# Supply.net
KiCad netlist of a schematic drawn in Altium Designer
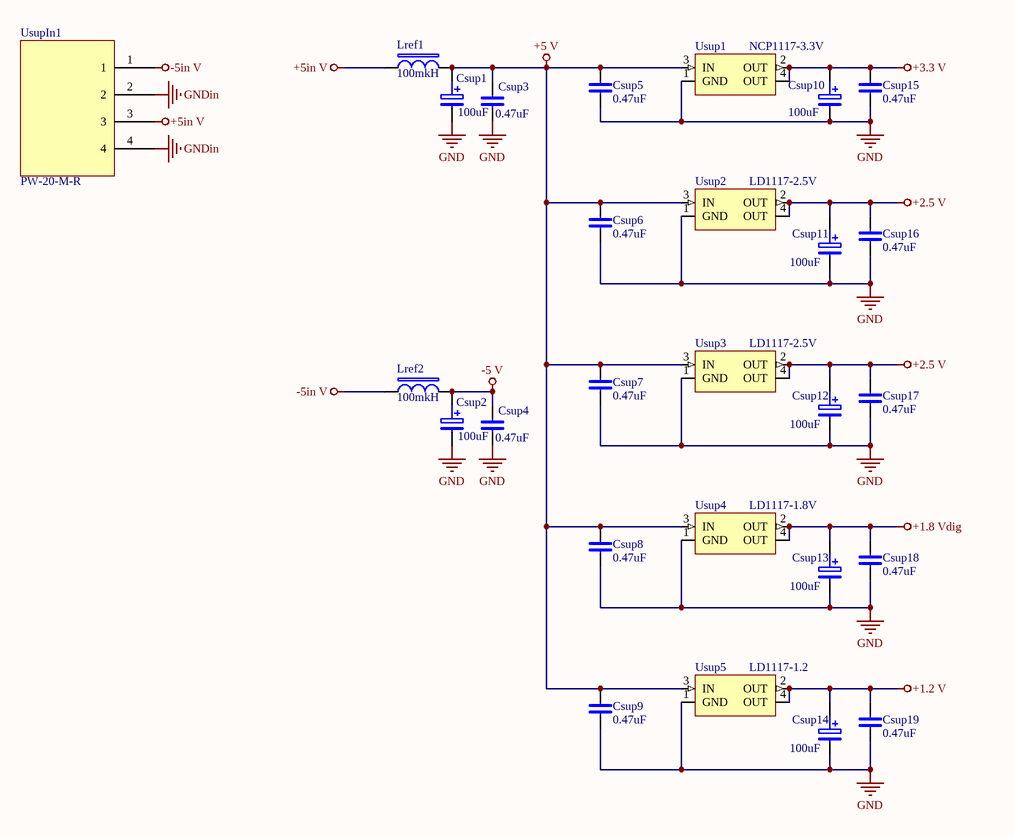
[diagram p0: Supply.SchDoc]

(export (version "E")
  (design (tool "Eeschema 10.0.6"))
  (components
    (comp (ref "Csup1") (value "100uF") (footprint "CEL-SMD300") (libsource (lib "*") (part "C POL")))
    (comp (ref "Csup2") (value "100uF") (footprint "CEL-SMD300") (libsource (lib "*") (part "C POL")))
    (comp (ref "Csup3") (value "0.47uF") (footprint "chip0603") (libsource (lib "*") (part "C")))
    (comp (ref "Csup4") (value "0.47uF") (footprint "chip0603") (libsource (lib "*") (part "C")))
    (comp (ref "Csup5") (value "0.47uF") (footprint "chip0603") (libsource (lib "*") (part "C")))
    (comp (ref "Csup6") (value "0.47uF") (footprint "chip0603") (libsource (lib "*") (part "C")))
    (comp (ref "Csup7") (value "0.47uF") (footprint "chip0603") (libsource (lib "*") (part "C")))
    (comp (ref "Csup8") (value "0.47uF") (footprint "chip0603") (libsource (lib "*") (part "C")))
    (comp (ref "Csup9") (value "0.47uF") (footprint "chip0603") (libsource (lib "*") (part "C")))
    (comp (ref "Csup10") (value "100uF") (footprint "CEL-SMD300") (libsource (lib "*") (part "C POL")))
    (comp (ref "Csup11") (value "100uF") (footprint "CEL-SMD300") (libsource (lib "*") (part "C POL")))
    (comp (ref "Csup12") (value "100uF") (footprint "CEL-SMD300") (libsource (lib "*") (part "C POL")))
    (comp (ref "Csup13") (value "100uF") (footprint "CEL-SMD300") (libsource (lib "*") (part "C POL")))
    (comp (ref "Csup14") (value "100uF") (footprint "CEL-SMD300") (libsource (lib "*") (part "C POL")))
    (comp (ref "Csup15") (value "0.47uF") (footprint "chip0603") (libsource (lib "*") (part "C")))
    (comp (ref "Csup16") (value "0.47uF") (footprint "chip0603") (libsource (lib "*") (part "C")))
    (comp (ref "Csup17") (value "0.47uF") (footprint "chip0603") (libsource (lib "*") (part "C")))
    (comp (ref "Csup18") (value "0.47uF") (footprint "chip0603") (libsource (lib "*") (part "C")))
    (comp (ref "Csup19") (value "0.47uF") (footprint "chip0603") (libsource (lib "*") (part "C")))
    (comp (ref "Lref1") (value "100mkH") (footprint "SDR0604") (libsource (lib "*") (part "DR")))
    (comp (ref "Lref2") (value "100mkH") (footprint "SDR0604") (libsource (lib "*") (part "DR")))
    (comp (ref "Usup1")
      (value "NCP1117-3.3V")
      (footprint "TO-252")
      (libsource (lib "vAnalog") (part "NCP1117-3.3V"))
    )
    (comp (ref "Usup2")
      (value "LD1117-2.5V")
      (footprint "TO-252")
      (libsource (lib "vAnalog") (part "NCP1117-3.3V"))
    )
    (comp (ref "Usup3")
      (value "LD1117-2.5V")
      (footprint "TO-252")
      (libsource (lib "vAnalog") (part "NCP1117-3.3V"))
    )
    (comp (ref "Usup4")
      (value "LD1117-1.8V")
      (footprint "TO-252")
      (libsource (lib "vAnalog") (part "NCP1117-3.3V"))
    )
    (comp (ref "Usup5")
      (value "LD1117-1.2")
      (footprint "TO-252")
      (libsource (lib "vAnalog") (part "NCP1117-3.3V"))
    )
    (comp (ref "UsupIn1")
      (value "PW-20-M-R")
      (footprint "PW20-M-R")
      (libsource (lib "vDevice") (part "PW-20-M-R"))
    )
  )
  (nets
    (net (code "1") (name "+1.2 V") (class "Default")
      (node (ref "Csup14") (pin "+") (pinfunction "+_+") (pintype "passive"))
      (node (ref "Csup19") (pin "1") (pinfunction "1_1") (pintype "passive"))
      (node (ref "Usup5") (pin "2") (pinfunction "OUT_2") (pintype "output"))
      (node (ref "Usup5") (pin "4") (pinfunction "OUT_4") (pintype "passive"))
    )
    (net (code "2") (name "+1.8 Vdig") (class "Default")
      (node (ref "Csup13") (pin "+") (pinfunction "+_+") (pintype "passive"))
      (node (ref "Csup18") (pin "1") (pinfunction "1_1") (pintype "passive"))
      (node (ref "Usup4") (pin "2") (pinfunction "OUT_2") (pintype "output"))
      (node (ref "Usup4") (pin "4") (pinfunction "OUT_4") (pintype "passive"))
    )
    (net (code "3") (name "+2.5 V") (class "Default")
      (node (ref "Csup11") (pin "+") (pinfunction "+_+") (pintype "passive"))
      (node (ref "Csup12") (pin "+") (pinfunction "+_+") (pintype "passive"))
      (node (ref "Csup16") (pin "1") (pinfunction "1_1") (pintype "passive"))
      (node (ref "Csup17") (pin "1") (pinfunction "1_1") (pintype "passive"))
      (node (ref "Usup2") (pin "2") (pinfunction "OUT_2") (pintype "output"))
      (node (ref "Usup2") (pin "4") (pinfunction "OUT_4") (pintype "passive"))
      (node (ref "Usup3") (pin "2") (pinfunction "OUT_2") (pintype "output"))
      (node (ref "Usup3") (pin "4") (pinfunction "OUT_4") (pintype "passive"))
    )
    (net (code "4") (name "+3.3 V") (class "Default")
      (node (ref "Csup10") (pin "+") (pinfunction "+_+") (pintype "passive"))
      (node (ref "Csup15") (pin "1") (pinfunction "1_1") (pintype "passive"))
      (node (ref "Usup1") (pin "2") (pinfunction "OUT_2") (pintype "output"))
      (node (ref "Usup1") (pin "4") (pinfunction "OUT_4") (pintype "passive"))
    )
    (net (code "5") (name "+5 V") (class "Default")
      (node (ref "Csup1") (pin "+") (pinfunction "+_+") (pintype "passive"))
      (node (ref "Csup3") (pin "1") (pinfunction "1_1") (pintype "passive"))
      (node (ref "Csup5") (pin "1") (pinfunction "1_1") (pintype "passive"))
      (node (ref "Csup6") (pin "1") (pinfunction "1_1") (pintype "passive"))
      (node (ref "Csup7") (pin "1") (pinfunction "1_1") (pintype "passive"))
      (node (ref "Csup8") (pin "1") (pinfunction "1_1") (pintype "passive"))
      (node (ref "Csup9") (pin "1") (pinfunction "1_1") (pintype "passive"))
      (node (ref "Lref1") (pin "2") (pinfunction "2_2") (pintype "passive"))
      (node (ref "Usup1") (pin "3") (pinfunction "IN_3") (pintype "input"))
      (node (ref "Usup2") (pin "3") (pinfunction "IN_3") (pintype "input"))
      (node (ref "Usup3") (pin "3") (pinfunction "IN_3") (pintype "input"))
      (node (ref "Usup4") (pin "3") (pinfunction "IN_3") (pintype "input"))
      (node (ref "Usup5") (pin "3") (pinfunction "IN_3") (pintype "input"))
    )
    (net (code "6") (name "+5in V") (class "Default")
      (node (ref "Lref1") (pin "1") (pinfunction "1_1") (pintype "passive"))
      (node (ref "UsupIn1") (pin "3") (pinfunction "3_3") (pintype "passive"))
    )
    (net (code "7") (name "-5 V") (class "Default")
      (node (ref "Csup2") (pin "+") (pinfunction "+_+") (pintype "passive"))
      (node (ref "Csup4") (pin "1") (pinfunction "1_1") (pintype "passive"))
      (node (ref "Lref2") (pin "2") (pinfunction "2_2") (pintype "passive"))
    )
    (net (code "8") (name "-5in V") (class "Default")
      (node (ref "Lref2") (pin "1") (pinfunction "1_1") (pintype "passive"))
      (node (ref "UsupIn1") (pin "1") (pinfunction "1_1") (pintype "passive"))
    )
    (net (code "9") (name "GND") (class "Default")
      (node (ref "Csup1") (pin "-") (pinfunction "-_-") (pintype "passive"))
      (node (ref "Csup10") (pin "-") (pinfunction "-_-") (pintype "passive"))
      (node (ref "Csup11") (pin "-") (pinfunction "-_-") (pintype "passive"))
      (node (ref "Csup12") (pin "-") (pinfunction "-_-") (pintype "passive"))
      (node (ref "Csup13") (pin "-") (pinfunction "-_-") (pintype "passive"))
      (node (ref "Csup14") (pin "-") (pinfunction "-_-") (pintype "passive"))
      (node (ref "Csup15") (pin "2") (pinfunction "2_2") (pintype "passive"))
      (node (ref "Csup16") (pin "2") (pinfunction "2_2") (pintype "passive"))
      (node (ref "Csup17") (pin "2") (pinfunction "2_2") (pintype "passive"))
      (node (ref "Csup18") (pin "2") (pinfunction "2_2") (pintype "passive"))
      (node (ref "Csup19") (pin "2") (pinfunction "2_2") (pintype "passive"))
      (node (ref "Csup2") (pin "-") (pinfunction "-_-") (pintype "passive"))
      (node (ref "Csup3") (pin "2") (pinfunction "2_2") (pintype "passive"))
      (node (ref "Csup4") (pin "2") (pinfunction "2_2") (pintype "passive"))
      (node (ref "Csup5") (pin "2") (pinfunction "2_2") (pintype "passive"))
      (node (ref "Csup6") (pin "2") (pinfunction "2_2") (pintype "passive"))
      (node (ref "Csup7") (pin "2") (pinfunction "2_2") (pintype "passive"))
      (node (ref "Csup8") (pin "2") (pinfunction "2_2") (pintype "passive"))
      (node (ref "Csup9") (pin "2") (pinfunction "2_2") (pintype "passive"))
      (node (ref "Usup1") (pin "1") (pinfunction "GND_1") (pintype "power_in"))
      (node (ref "Usup2") (pin "1") (pinfunction "GND_1") (pintype "power_in"))
      (node (ref "Usup3") (pin "1") (pinfunction "GND_1") (pintype "power_in"))
      (node (ref "Usup4") (pin "1") (pinfunction "GND_1") (pintype "power_in"))
      (node (ref "Usup5") (pin "1") (pinfunction "GND_1") (pintype "power_in"))
    )
    (net (code "10") (name "GNDin") (class "Default")
      (node (ref "UsupIn1") (pin "2") (pinfunction "2_2") (pintype "passive"))
      (node (ref "UsupIn1") (pin "4") (pinfunction "4_4") (pintype "passive"))
    )
  )
)
